# SCH_USB-Hub_2025-02-04.net
KiCad netlist of a schematic drawn in EasyEDA
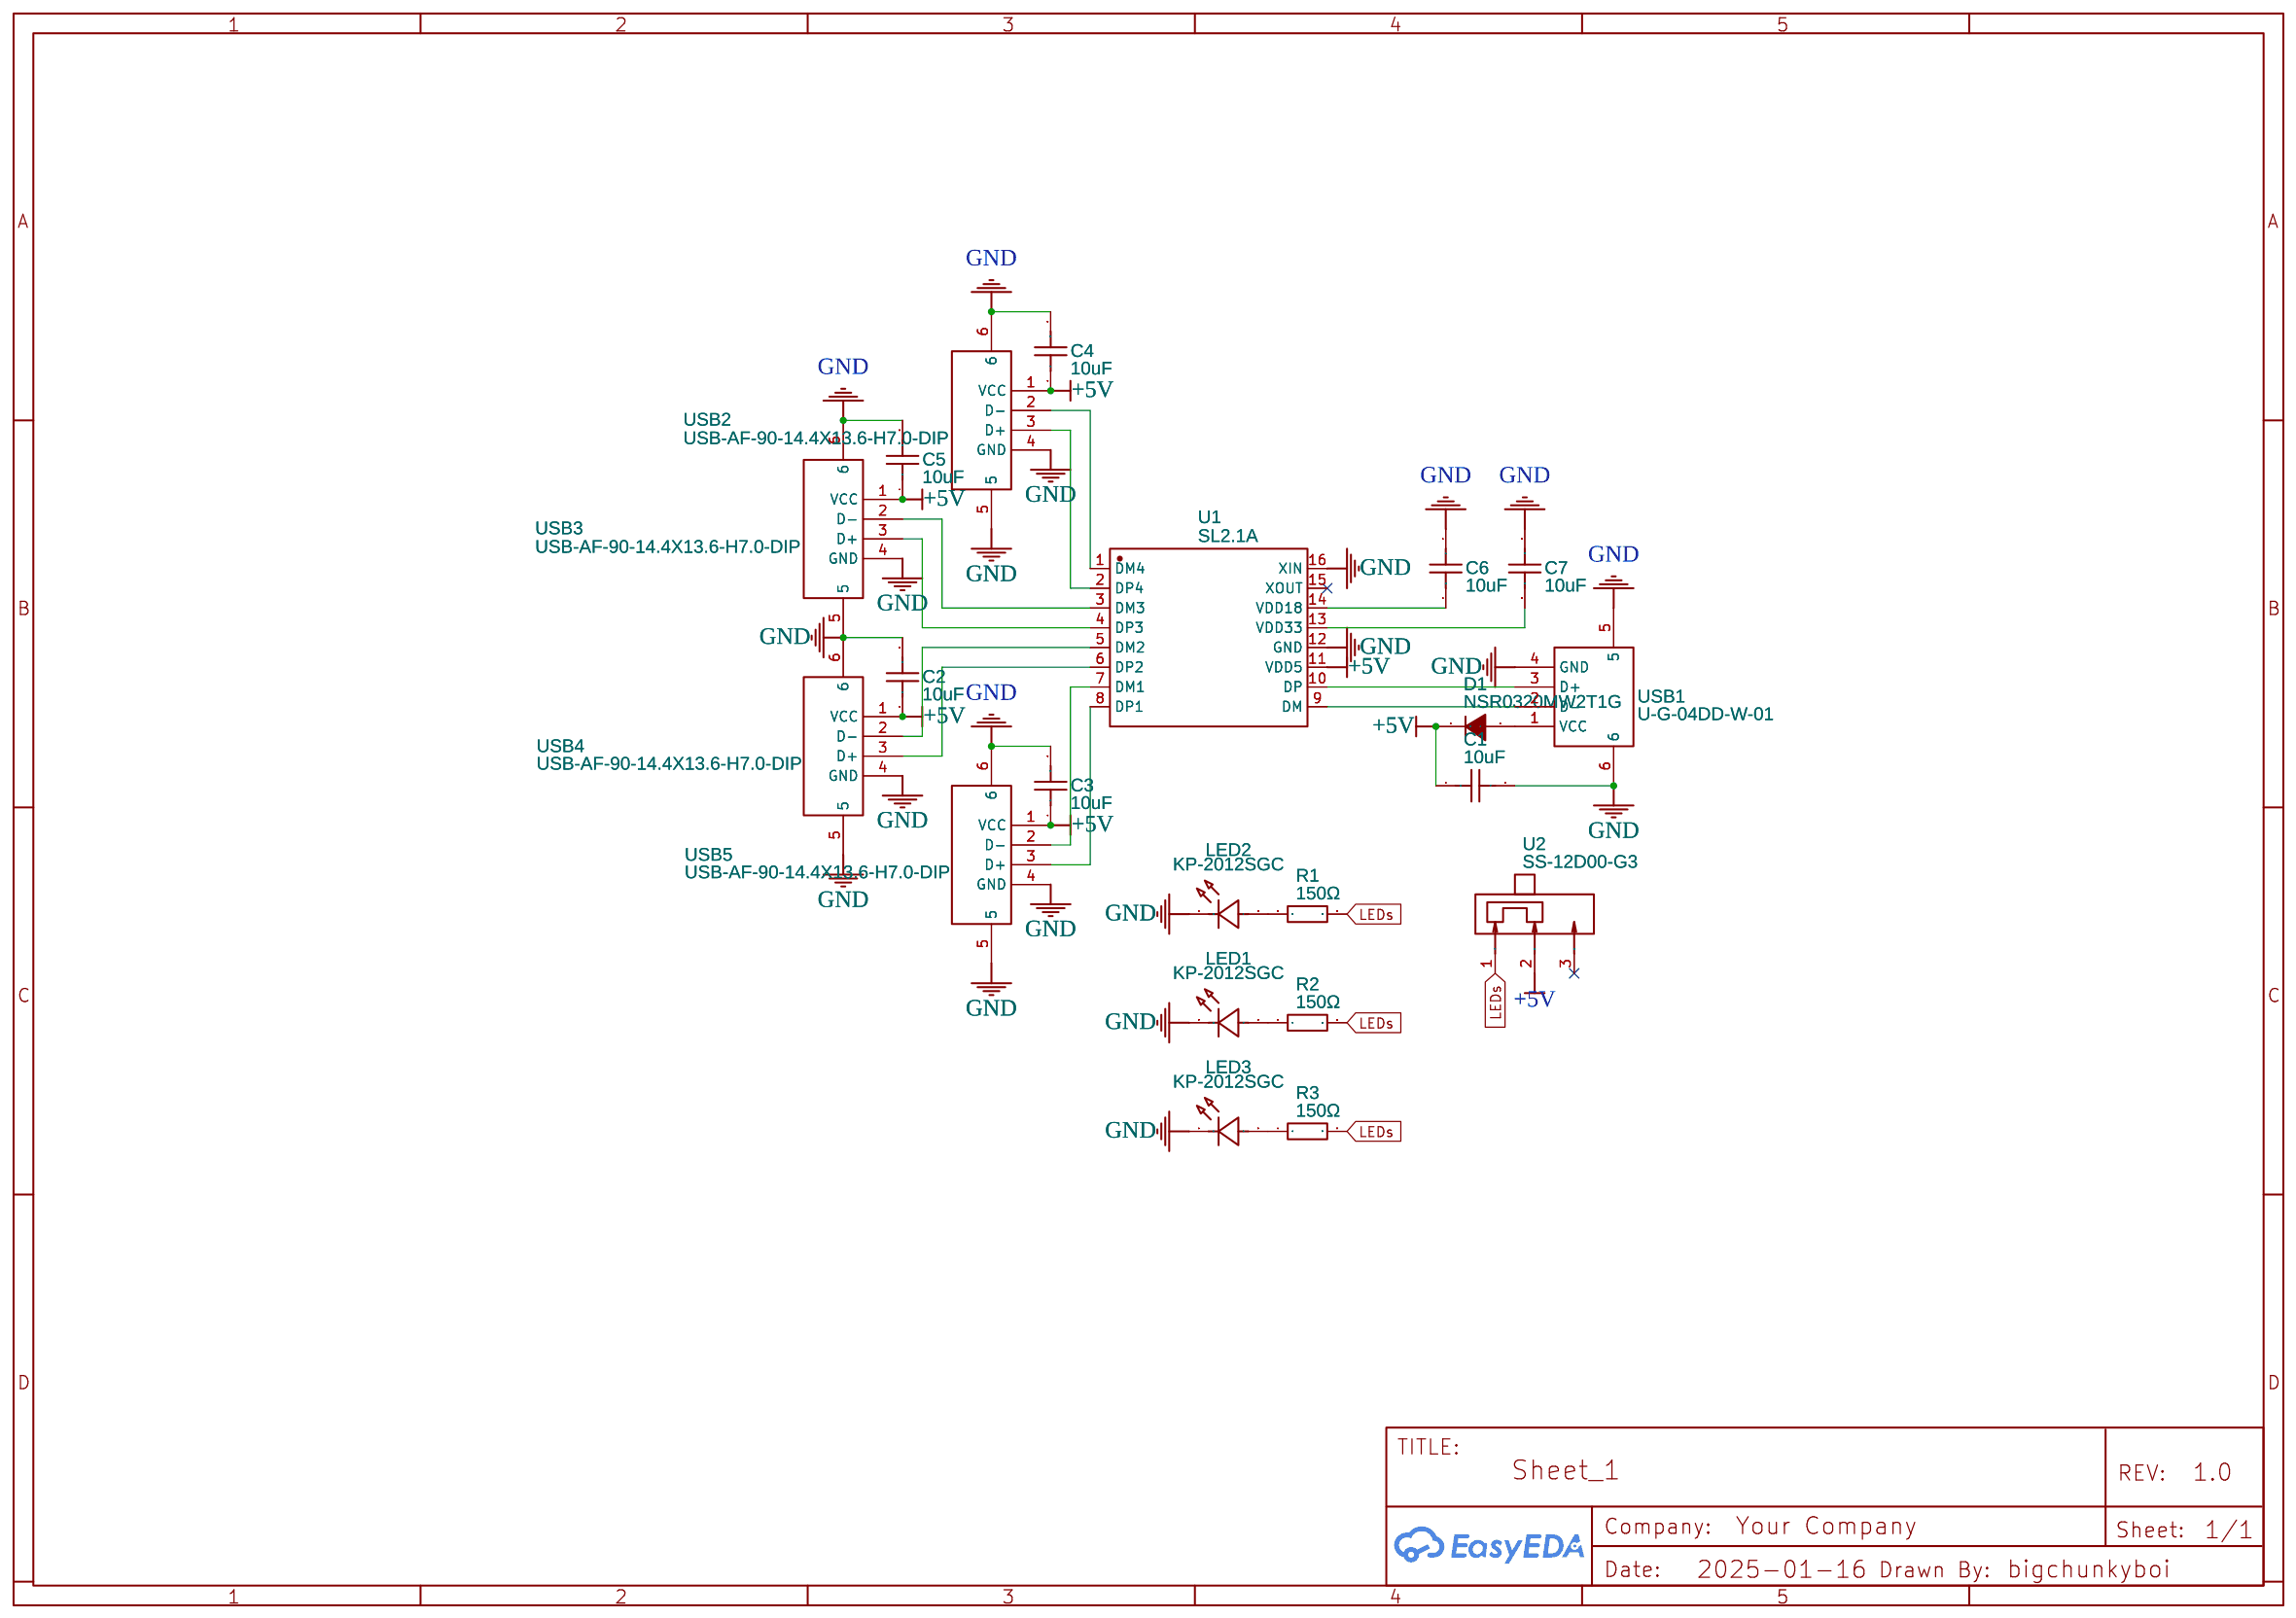
[diagram p0: schematic sheet]

(export (version "E")
  (design (tool "Eeschema 10.0.6"))
  (components
    (comp (ref "C1")
      (value "10uF")
      (fields
        (field (name "Manufacturer Part") "CL10A106KP8NNNC")
        (field (name "Manufacturer") "SAMSUNG(三星)")
      )
      (libsource (lib "") (part "CL10A106KP8NNNC_1"))
    )
    (comp (ref "C2")
      (value "10uF")
      (fields
        (field (name "Manufacturer Part") "CL10A106KP8NNNC")
        (field (name "Manufacturer") "SAMSUNG(三星)")
      )
      (libsource (lib "") (part "CL10A106KP8NNNC"))
    )
    (comp (ref "C3")
      (value "10uF")
      (fields
        (field (name "Manufacturer Part") "CL10A106KP8NNNC")
        (field (name "Manufacturer") "SAMSUNG(三星)")
      )
      (libsource (lib "") (part "CL10A106KP8NNNC"))
    )
    (comp (ref "C4")
      (value "10uF")
      (fields
        (field (name "Manufacturer Part") "CL10A106KP8NNNC")
        (field (name "Manufacturer") "SAMSUNG(三星)")
      )
      (libsource (lib "") (part "CL10A106KP8NNNC"))
    )
    (comp (ref "C5")
      (value "10uF")
      (fields
        (field (name "Manufacturer Part") "CL10A106KP8NNNC")
        (field (name "Manufacturer") "SAMSUNG(三星)")
      )
      (libsource (lib "") (part "CL10A106KP8NNNC"))
    )
    (comp (ref "C6")
      (value "10uF")
      (fields
        (field (name "Manufacturer Part") "CL10A106KP8NNNC")
        (field (name "Manufacturer") "SAMSUNG(三星)")
      )
      (libsource (lib "") (part "CL10A106KP8NNNC_2"))
    )
    (comp (ref "C7")
      (value "10uF")
      (fields
        (field (name "Manufacturer Part") "CL10A106KP8NNNC")
        (field (name "Manufacturer") "SAMSUNG(三星)")
      )
      (libsource (lib "") (part "CL10A106KP8NNNC_2"))
    )
    (comp (ref "D1")
      (value "NSR0320MW2T1G")
      (fields (field (name "Manufacturer") "onsemi(安森美)"))
      (libsource (lib "") (part "NSR0320MW2T1G"))
    )
    (comp (ref "LED1")
      (value "KP-2012SGC")
      (fields (field (name "Manufacturer") "Kingbright"))
      (libsource (lib "") (part "KP-2012SGC"))
    )
    (comp (ref "LED2")
      (value "KP-2012SGC")
      (fields (field (name "Manufacturer") "Kingbright"))
      (libsource (lib "") (part "KP-2012SGC"))
    )
    (comp (ref "LED3")
      (value "KP-2012SGC")
      (fields (field (name "Manufacturer") "Kingbright"))
      (libsource (lib "") (part "KP-2012SGC"))
    )
    (comp (ref "R1")
      (value "150Ω")
      (fields (field (name "Manufacturer Part") "RC0603FR-07150RL") (field (name "Manufacturer") "YAGEO(国巨)"))
      (libsource (lib "") (part "RC0603FR-07150RL"))
    )
    (comp (ref "R2")
      (value "150Ω")
      (fields (field (name "Manufacturer Part") "RC0603FR-07150RL") (field (name "Manufacturer") "YAGEO(国巨)"))
      (libsource (lib "") (part "RC0603FR-07150RL"))
    )
    (comp (ref "R3")
      (value "150Ω")
      (fields (field (name "Manufacturer Part") "RC0603FR-07150RL") (field (name "Manufacturer") "YAGEO(国巨)"))
      (libsource (lib "") (part "RC0603FR-07150RL"))
    )
    (comp (ref "U1")
      (value "SL2.1A")
      (fields (field (name "Manufacturer") "CoreChips(和芯润德)"))
      (libsource (lib "") (part "SL2.1A"))
    )
    (comp (ref "U2")
      (value "SS-12D00-G3")
      (fields (field (name "Manufacturer") "SOFNG(硕方)"))
      (libsource (lib "") (part "SS-12D00-G3"))
    )
    (comp (ref "USB1")
      (value "U-G-04DD-W-01")
      (fields (field (name "Manufacturer Part") "U-G-O4DD-W-1") (field (name "Manufacturer") "韩国韩荣"))
      (libsource (lib "") (part "U-G-04DD-W-01"))
    )
    (comp (ref "USB2")
      (value "USB-AF-90-14.4X13.6-H7.0-DIP")
      (fields (field (name "Manufacturer Part") "903-131A1011D10100") (field (name "Manufacturer") "精拓金"))
      (libsource (lib "") (part "USB-AF-90-14.4X13.6-H7.0-DIP"))
    )
    (comp (ref "USB3")
      (value "USB-AF-90-14.4X13.6-H7.0-DIP")
      (fields (field (name "Manufacturer Part") "903-131A1011D10100") (field (name "Manufacturer") "精拓金"))
      (libsource (lib "") (part "USB-AF-90-14.4X13.6-H7.0-DIP"))
    )
    (comp (ref "USB4")
      (value "USB-AF-90-14.4X13.6-H7.0-DIP")
      (fields (field (name "Manufacturer Part") "903-131A1011D10100") (field (name "Manufacturer") "精拓金"))
      (libsource (lib "") (part "USB-AF-90-14.4X13.6-H7.0-DIP"))
    )
    (comp (ref "USB5")
      (value "USB-AF-90-14.4X13.6-H7.0-DIP")
      (fields (field (name "Manufacturer Part") "903-131A1011D10100") (field (name "Manufacturer") "精拓金"))
      (libsource (lib "") (part "USB-AF-90-14.4X13.6-H7.0-DIP"))
    )
  )
  (nets
    (net (code "1") (name "+5V") (class "Default")
      (node (ref "C1") (pin "1") (pinfunction "1_1") (pintype "unspecified"))
      (node (ref "C2") (pin "1") (pinfunction "1_1") (pintype "unspecified"))
      (node (ref "C3") (pin "1") (pinfunction "1_1") (pintype "unspecified"))
      (node (ref "C4") (pin "1") (pinfunction "1_1") (pintype "unspecified"))
      (node (ref "C5") (pin "1") (pinfunction "1_1") (pintype "unspecified"))
      (node (ref "D1") (pin "1") (pinfunction "C_1") (pintype "unspecified"))
      (node (ref "U1") (pin "11") (pinfunction "VDD5_11") (pintype "unspecified"))
      (node (ref "U2") (pin "2") (pinfunction "2_2") (pintype "unspecified"))
      (node (ref "USB2") (pin "1") (pinfunction "VCC_1") (pintype "unspecified"))
      (node (ref "USB3") (pin "1") (pinfunction "VCC_1") (pintype "unspecified"))
      (node (ref "USB4") (pin "1") (pinfunction "VCC_1") (pintype "unspecified"))
      (node (ref "USB5") (pin "1") (pinfunction "VCC_1") (pintype "unspecified"))
    )
    (net (code "2") (name "GND") (class "Default")
      (node (ref "C1") (pin "2") (pinfunction "2_2") (pintype "unspecified"))
      (node (ref "C2") (pin "2") (pinfunction "2_2") (pintype "unspecified"))
      (node (ref "C3") (pin "2") (pinfunction "2_2") (pintype "unspecified"))
      (node (ref "C4") (pin "2") (pinfunction "2_2") (pintype "unspecified"))
      (node (ref "C5") (pin "2") (pinfunction "2_2") (pintype "unspecified"))
      (node (ref "C6") (pin "1") (pinfunction "1_1") (pintype "unspecified"))
      (node (ref "C7") (pin "1") (pinfunction "1_1") (pintype "unspecified"))
      (node (ref "LED1") (pin "1") (pinfunction "K_1") (pintype "unspecified"))
      (node (ref "LED2") (pin "1") (pinfunction "K_1") (pintype "unspecified"))
      (node (ref "LED3") (pin "1") (pinfunction "K_1") (pintype "unspecified"))
      (node (ref "U1") (pin "12") (pinfunction "GND_12") (pintype "unspecified"))
      (node (ref "U1") (pin "16") (pinfunction "XIN_16") (pintype "unspecified"))
      (node (ref "USB1") (pin "4") (pinfunction "GND_4") (pintype "unspecified"))
      (node (ref "USB1") (pin "5") (pinfunction "5_5") (pintype "unspecified"))
      (node (ref "USB1") (pin "6") (pinfunction "6_6") (pintype "unspecified"))
      (node (ref "USB2") (pin "4") (pinfunction "GND_4") (pintype "unspecified"))
      (node (ref "USB2") (pin "5") (pinfunction "5_5") (pintype "unspecified"))
      (node (ref "USB2") (pin "6") (pinfunction "6_6") (pintype "unspecified"))
      (node (ref "USB3") (pin "4") (pinfunction "GND_4") (pintype "unspecified"))
      (node (ref "USB3") (pin "5") (pinfunction "5_5") (pintype "unspecified"))
      (node (ref "USB3") (pin "6") (pinfunction "6_6") (pintype "unspecified"))
      (node (ref "USB4") (pin "4") (pinfunction "GND_4") (pintype "unspecified"))
      (node (ref "USB4") (pin "5") (pinfunction "5_5") (pintype "unspecified"))
      (node (ref "USB4") (pin "6") (pinfunction "6_6") (pintype "unspecified"))
      (node (ref "USB5") (pin "4") (pinfunction "GND_4") (pintype "unspecified"))
      (node (ref "USB5") (pin "5") (pinfunction "5_5") (pintype "unspecified"))
      (node (ref "USB5") (pin "6") (pinfunction "6_6") (pintype "unspecified"))
    )
    (net (code "3") (name "LEDs") (class "Default")
      (node (ref "R1") (pin "2") (pinfunction "2_2") (pintype "input"))
      (node (ref "R2") (pin "2") (pinfunction "2_2") (pintype "input"))
      (node (ref "R3") (pin "2") (pinfunction "2_2") (pintype "input"))
      (node (ref "U2") (pin "1") (pinfunction "1_1") (pintype "unspecified"))
    )
    (net (code "4") (name "Net-(D1-A)") (class "Default")
      (node (ref "D1") (pin "2") (pinfunction "A_2") (pintype "unspecified"))
      (node (ref "USB1") (pin "1") (pinfunction "VCC_1") (pintype "unspecified"))
    )
    (net (code "5") (name "Net-(LED1-A)") (class "Default")
      (node (ref "LED1") (pin "2") (pinfunction "A_2") (pintype "unspecified"))
      (node (ref "R2") (pin "1") (pinfunction "1_1") (pintype "input"))
    )
    (net (code "6") (name "Net-(LED2-A)") (class "Default")
      (node (ref "LED2") (pin "2") (pinfunction "A_2") (pintype "unspecified"))
      (node (ref "R1") (pin "1") (pinfunction "1_1") (pintype "input"))
    )
    (net (code "7") (name "Net-(LED3-A)") (class "Default")
      (node (ref "LED3") (pin "2") (pinfunction "A_2") (pintype "unspecified"))
      (node (ref "R3") (pin "1") (pinfunction "1_1") (pintype "input"))
    )
    (net (code "8") (name "Net-(U1-DM)") (class "Default")
      (node (ref "U1") (pin "9") (pinfunction "DM_9") (pintype "unspecified"))
      (node (ref "USB1") (pin "2") (pinfunction "D-_2") (pintype "unspecified"))
    )
    (net (code "9") (name "Net-(U1-DM1)") (class "Default")
      (node (ref "U1") (pin "7") (pinfunction "DM1_7") (pintype "unspecified"))
      (node (ref "USB5") (pin "2") (pinfunction "D-_2") (pintype "unspecified"))
    )
    (net (code "10") (name "Net-(U1-DM2)") (class "Default")
      (node (ref "U1") (pin "5") (pinfunction "DM2_5") (pintype "unspecified"))
      (node (ref "USB4") (pin "2") (pinfunction "D-_2") (pintype "unspecified"))
    )
    (net (code "11") (name "Net-(U1-DM3)") (class "Default")
      (node (ref "U1") (pin "3") (pinfunction "DM3_3") (pintype "unspecified"))
      (node (ref "USB3") (pin "2") (pinfunction "D-_2") (pintype "unspecified"))
    )
    (net (code "12") (name "Net-(U1-DM4)") (class "Default")
      (node (ref "U1") (pin "1") (pinfunction "DM4_1") (pintype "unspecified"))
      (node (ref "USB2") (pin "2") (pinfunction "D-_2") (pintype "unspecified"))
    )
    (net (code "13") (name "Net-(U1-DP)") (class "Default")
      (node (ref "U1") (pin "10") (pinfunction "DP_10") (pintype "unspecified"))
      (node (ref "USB1") (pin "3") (pinfunction "D+_3") (pintype "unspecified"))
    )
    (net (code "14") (name "Net-(U1-DP1)") (class "Default")
      (node (ref "U1") (pin "8") (pinfunction "DP1_8") (pintype "unspecified"))
      (node (ref "USB5") (pin "3") (pinfunction "D+_3") (pintype "unspecified"))
    )
    (net (code "15") (name "Net-(U1-DP2)") (class "Default")
      (node (ref "U1") (pin "6") (pinfunction "DP2_6") (pintype "unspecified"))
      (node (ref "USB4") (pin "3") (pinfunction "D+_3") (pintype "unspecified"))
    )
    (net (code "16") (name "Net-(U1-DP3)") (class "Default")
      (node (ref "U1") (pin "4") (pinfunction "DP3_4") (pintype "unspecified"))
      (node (ref "USB3") (pin "3") (pinfunction "D+_3") (pintype "unspecified"))
    )
    (net (code "17") (name "Net-(U1-DP4)") (class "Default")
      (node (ref "U1") (pin "2") (pinfunction "DP4_2") (pintype "unspecified"))
      (node (ref "USB2") (pin "3") (pinfunction "D+_3") (pintype "unspecified"))
    )
    (net (code "18") (name "Net-(U1-VDD18)") (class "Default")
      (node (ref "C6") (pin "2") (pinfunction "2_2") (pintype "unspecified"))
      (node (ref "U1") (pin "14") (pinfunction "VDD18_14") (pintype "unspecified"))
    )
    (net (code "19") (name "Net-(U1-VDD33)") (class "Default")
      (node (ref "C7") (pin "2") (pinfunction "2_2") (pintype "unspecified"))
      (node (ref "U1") (pin "13") (pinfunction "VDD33_13") (pintype "unspecified"))
    )
    (net (code "20") (name "unconnected-(U1-XOUT-Pad15)") (class "Default")
      (node (ref "U1") (pin "15") (pinfunction "XOUT_15") (pintype "unspecified+no_connect"))
    )
    (net (code "21") (name "unconnected-(U2-Pad3)") (class "Default")
      (node (ref "U2") (pin "3") (pinfunction "3_3") (pintype "unspecified+no_connect"))
    )
  )
)
